# Sheet1.net
KiCad netlist of a schematic drawn in Altium Designer
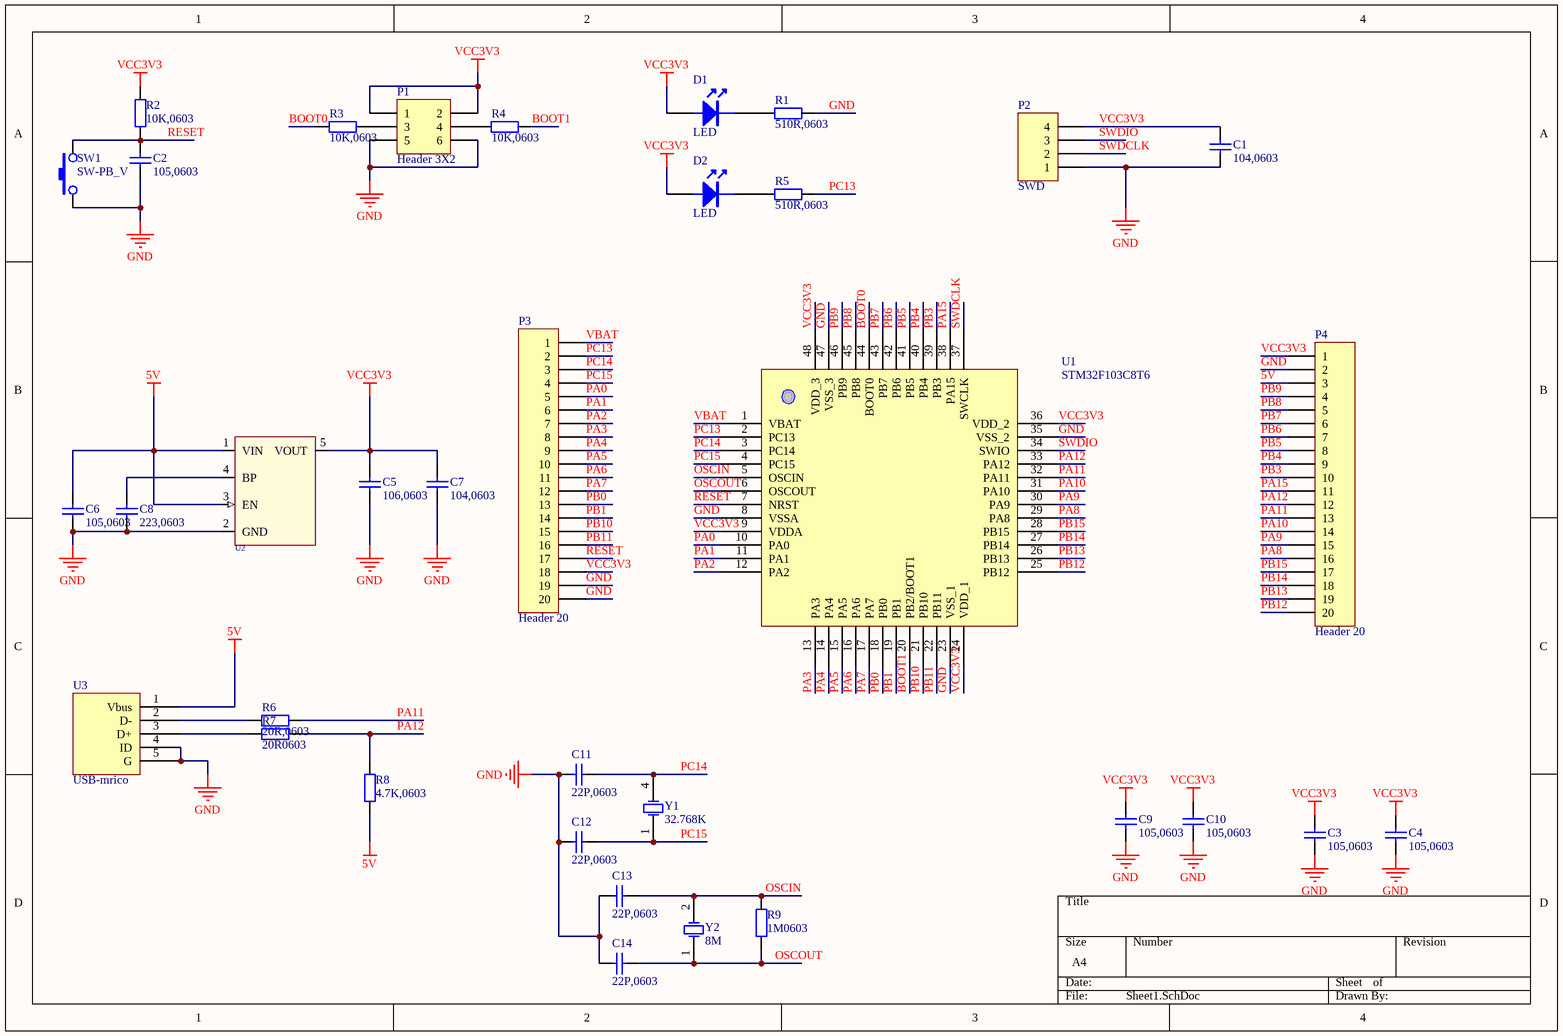
[diagram p0: Sheet1.SchDoc]

(export (version "E")
  (design (tool "Eeschema 10.0.6"))
  (components
    (comp (ref "C1")
      (value "104,0603")
      (footprint "C 0603")
      (description "Capacitor")
      (fields (field (name "PUBLISHER") "Altium Limited"))
      (libsource (lib "STM32F103C8T6") (part "Cap"))
    )
    (comp (ref "C2")
      (value "105,0603")
      (footprint "C 0603")
      (description "Capacitor")
      (fields (field (name "PUBLISHER") "Altium Limited"))
      (libsource (lib "STM32F103C8T6") (part "Cap"))
    )
    (comp (ref "C3")
      (value "105,0603")
      (footprint "C 0603")
      (description "Capacitor")
      (fields (field (name "PUBLISHER") "Altium Limited"))
      (libsource (lib "STM32F103C8T6") (part "Cap"))
    )
    (comp (ref "C4")
      (value "105,0603")
      (footprint "C 0603")
      (description "Capacitor")
      (fields (field (name "PUBLISHER") "Altium Limited"))
      (libsource (lib "STM32F103C8T6") (part "Cap"))
    )
    (comp (ref "C5")
      (value "106,0603")
      (footprint "C 0603")
      (description "Capacitor")
      (fields (field (name "PUBLISHER") "Altium Limited"))
      (libsource (lib "STM32F103C8T6") (part "Cap"))
    )
    (comp (ref "C6")
      (value "105,0603")
      (footprint "C 0603")
      (description "Capacitor")
      (fields (field (name "PUBLISHER") "Altium Limited"))
      (libsource (lib "STM32F103C8T6") (part "Cap"))
    )
    (comp (ref "C7")
      (value "104,0603")
      (footprint "C 0603")
      (description "Capacitor")
      (fields (field (name "PUBLISHER") "Altium Limited"))
      (libsource (lib "STM32F103C8T6") (part "Cap"))
    )
    (comp (ref "C8")
      (value "223,0603")
      (footprint "C 0603")
      (description "Capacitor")
      (fields (field (name "PUBLISHER") "Altium Limited"))
      (libsource (lib "STM32F103C8T6") (part "Cap"))
    )
    (comp (ref "C9")
      (value "105,0603")
      (footprint "C 0603")
      (description "Capacitor")
      (fields (field (name "PUBLISHER") "Altium Limited"))
      (libsource (lib "STM32F103C8T6") (part "Cap"))
    )
    (comp (ref "C10")
      (value "105,0603")
      (footprint "C 0603")
      (description "Capacitor")
      (fields (field (name "PUBLISHER") "Altium Limited"))
      (libsource (lib "STM32F103C8T6") (part "Cap"))
    )
    (comp (ref "C11")
      (value "22P,0603")
      (footprint "C 0603")
      (description "Capacitor")
      (fields (field (name "PUBLISHER") "Altium Limited"))
      (libsource (lib "STM32F103C8T6") (part "Cap"))
    )
    (comp (ref "C12")
      (value "22P,0603")
      (footprint "C 0603")
      (description "Capacitor")
      (fields (field (name "PUBLISHER") "Altium Limited"))
      (libsource (lib "STM32F103C8T6") (part "Cap"))
    )
    (comp (ref "C13")
      (value "22P,0603")
      (footprint "C 0603")
      (description "Capacitor")
      (fields (field (name "PUBLISHER") "Altium Limited"))
      (libsource (lib "STM32F103C8T6") (part "Cap"))
    )
    (comp (ref "C14")
      (value "22P,0603")
      (footprint "C 0603")
      (description "Capacitor")
      (fields (field (name "PUBLISHER") "Altium Limited"))
      (libsource (lib "STM32F103C8T6") (part "Cap"))
    )
    (comp (ref "D1") (value "LED") (footprint "LED 0805G") (libsource (lib "STM32F103C8T6") (part "LED")))
    (comp (ref "D2") (value "LED") (footprint "LED 0805G") (libsource (lib "STM32F103C8T6") (part "LED")))
    (comp (ref "P1")
      (value "Header 3X2")
      (footprint "HDR-3X2")
      (description "Header, 3-Pin, Dual row")
      (fields (field (name "PUBLISHER") "Altium Limited"))
      (libsource (lib "STM32F103C8T6") (part "Header 3X2"))
    )
    (comp (ref "P2")
      (value "SWD")
      (footprint "HDR-1X4_H")
      (description "Header, 4-Pin")
      (fields (field (name "PUBLISHER") "Altium Limited"))
      (libsource (lib "STM32F103C8T6") (part "Header 4"))
    )
    (comp (ref "P3")
      (value "Header 20")
      (footprint "HDR1X20")
      (description "Header, 20-Pin")
      (fields (field (name "PUBLISHER") "Altium Limited"))
      (libsource (lib "STM32F103C8T6") (part "Header 20"))
    )
    (comp (ref "P4")
      (value "Header 20")
      (footprint "HDR1X20")
      (description "Header, 20-Pin")
      (fields (field (name "PUBLISHER") "Altium Limited"))
      (libsource (lib "") (part "Header 20_1"))
    )
    (comp (ref "R1")
      (value "510R,0603")
      (footprint "R 0603")
      (description "Resistor")
      (fields (field (name "PUBLISHER") "Altium Limited"))
      (libsource (lib "") (part "Res2_1"))
    )
    (comp (ref "R2")
      (value "10K,0603")
      (footprint "R 0603")
      (description "Resistor")
      (fields (field (name "PUBLISHER") "Altium Limited"))
      (libsource (lib "STM32F103C8T6") (part "Res2"))
    )
    (comp (ref "R3")
      (value "10K,0603")
      (footprint "R 0603")
      (description "Resistor")
      (fields (field (name "PUBLISHER") "Altium Limited"))
      (libsource (lib "") (part "Res2_1"))
    )
    (comp (ref "R4")
      (value "10K,0603")
      (footprint "R 0603")
      (description "Resistor")
      (fields (field (name "PUBLISHER") "Altium Limited"))
      (libsource (lib "") (part "Res2_1"))
    )
    (comp (ref "R5")
      (value "510R,0603")
      (footprint "R 0603")
      (description "Resistor")
      (fields (field (name "PUBLISHER") "Altium Limited"))
      (libsource (lib "") (part "Res2_1"))
    )
    (comp (ref "R6")
      (value "20R,0603")
      (footprint "R 0603")
      (description "Resistor")
      (fields (field (name "PUBLISHER") "Altium Limited"))
      (libsource (lib "") (part "Res2_1"))
    )
    (comp (ref "R7")
      (value "20R0603")
      (footprint "R 0603")
      (description "Resistor")
      (fields (field (name "PUBLISHER") "Altium Limited"))
      (libsource (lib "") (part "Res2_1"))
    )
    (comp (ref "R8")
      (value "4.7K,0603")
      (footprint "R 0603")
      (description "Resistor")
      (fields (field (name "PUBLISHER") "Altium Limited"))
      (libsource (lib "STM32F103C8T6") (part "Res2"))
    )
    (comp (ref "R9")
      (value "1M0603")
      (footprint "R 0603")
      (description "Resistor")
      (fields (field (name "PUBLISHER") "Altium Limited"))
      (libsource (lib "STM32F103C8T6") (part "Res2"))
    )
    (comp (ref "SW1")
      (value "SW-PB_V")
      (footprint "TSW SMD-3*6*2.5")
      (description "SWITCH")
      (libsource (lib "STM32F103C8T6") (part "SW-PB_V"))
    )
    (comp (ref "U1")
      (value "STM32F103C8T6")
      (footprint "TQFP48 7x7_L")
      (libsource (lib "STM32F103C8T6") (part "STM32F103C8T6"))
    )
    (comp (ref "U2")
      (value "RT9193")
      (footprint "SOT23-5L")
      (fields (field (name "ICA_PARTNUM") "$$2191094$$RT9193-15CU5") (field (name "PART NUMBER") "TMP-13"))
      (libsource (lib "STM32F103C8T6") (part "RT9193X_5P"))
    )
    (comp (ref "U3")
      (value "USB-mrico")
      (footprint "USB-micro_B")
      (libsource (lib "PCB_Project_4") (part "usb-STM"))
    )
    (comp (ref "Y1")
      (value "32.768K")
      (footprint "MC-306")
      (description "Crystal Oscillator")
      (fields (field (name "PUBLISHER") "Altium Limited"))
      (libsource (lib "STM32F103C8T6") (part "XTAL"))
    )
    (comp (ref "Y2")
      (value "8M")
      (footprint "XTAL-49S DIP")
      (description "Crystal Oscillator")
      (fields (field (name "PUBLISHER") "Altium Limited"))
      (libsource (lib "") (part "XTAL_1"))
    )
  )
  (nets
    (net (code "1") (name "/BOOT0") (class "Default")
      (node (ref "R3") (pin "1") (pinfunction "1_1") (pintype "passive"))
      (node (ref "U1") (pin "44") (pinfunction "BOOT0_44") (pintype "passive"))
    )
    (net (code "2") (name "/BOOT1") (class "Default")
      (node (ref "R4") (pin "2") (pinfunction "2_2") (pintype "passive"))
      (node (ref "U1") (pin "20") (pinfunction "PB2/BOOT1_20") (pintype "passive"))
    )
    (net (code "3") (name "/OSCIN") (class "Default")
      (node (ref "C13") (pin "1") (pinfunction "1_1") (pintype "passive"))
      (node (ref "R9") (pin "2") (pinfunction "2_2") (pintype "passive"))
      (node (ref "U1") (pin "5") (pinfunction "OSCIN_5") (pintype "passive"))
      (node (ref "Y2") (pin "2") (pinfunction "OSC2_2") (pintype "passive"))
    )
    (net (code "4") (name "/OSCOUT") (class "Default")
      (node (ref "C14") (pin "1") (pinfunction "1_1") (pintype "passive"))
      (node (ref "R9") (pin "1") (pinfunction "1_1") (pintype "passive"))
      (node (ref "U1") (pin "6") (pinfunction "OSCOUT_6") (pintype "passive"))
      (node (ref "Y2") (pin "1") (pinfunction "OSC1_1") (pintype "passive"))
    )
    (net (code "5") (name "/PA0") (class "Default")
      (node (ref "P3") (pin "5") (pinfunction "5_5") (pintype "passive"))
      (node (ref "U1") (pin "10") (pinfunction "PA0_10") (pintype "passive"))
    )
    (net (code "6") (name "/PA1") (class "Default")
      (node (ref "P3") (pin "6") (pinfunction "6_6") (pintype "passive"))
      (node (ref "U1") (pin "11") (pinfunction "PA1_11") (pintype "passive"))
    )
    (net (code "7") (name "/PA2") (class "Default")
      (node (ref "P3") (pin "7") (pinfunction "7_7") (pintype "passive"))
      (node (ref "U1") (pin "12") (pinfunction "PA2_12") (pintype "passive"))
    )
    (net (code "8") (name "/PA3") (class "Default")
      (node (ref "P3") (pin "8") (pinfunction "8_8") (pintype "passive"))
      (node (ref "U1") (pin "13") (pinfunction "PA3_13") (pintype "passive"))
    )
    (net (code "9") (name "/PA4") (class "Default")
      (node (ref "P3") (pin "9") (pinfunction "9_9") (pintype "passive"))
      (node (ref "U1") (pin "14") (pinfunction "PA4_14") (pintype "passive"))
    )
    (net (code "10") (name "/PA5") (class "Default")
      (node (ref "P3") (pin "10") (pinfunction "10_10") (pintype "passive"))
      (node (ref "U1") (pin "15") (pinfunction "PA5_15") (pintype "passive"))
    )
    (net (code "11") (name "/PA6") (class "Default")
      (node (ref "P3") (pin "11") (pinfunction "11_11") (pintype "passive"))
      (node (ref "U1") (pin "16") (pinfunction "PA6_16") (pintype "passive"))
    )
    (net (code "12") (name "/PA7") (class "Default")
      (node (ref "P3") (pin "12") (pinfunction "12_12") (pintype "passive"))
      (node (ref "U1") (pin "17") (pinfunction "PA7_17") (pintype "passive"))
    )
    (net (code "13") (name "/PA8") (class "Default")
      (node (ref "P4") (pin "16") (pinfunction "16_16") (pintype "passive"))
      (node (ref "U1") (pin "29") (pinfunction "PA8_29") (pintype "passive"))
    )
    (net (code "14") (name "/PA9") (class "Default")
      (node (ref "P4") (pin "15") (pinfunction "15_15") (pintype "passive"))
      (node (ref "U1") (pin "30") (pinfunction "PA9_30") (pintype "passive"))
    )
    (net (code "15") (name "/PA10") (class "Default")
      (node (ref "P4") (pin "14") (pinfunction "14_14") (pintype "passive"))
      (node (ref "U1") (pin "31") (pinfunction "PA10_31") (pintype "passive"))
    )
    (net (code "16") (name "/PA11") (class "Default")
      (node (ref "P4") (pin "13") (pinfunction "13_13") (pintype "passive"))
      (node (ref "R6") (pin "2") (pinfunction "2_2") (pintype "passive"))
      (node (ref "U1") (pin "32") (pinfunction "PA11_32") (pintype "passive"))
    )
    (net (code "17") (name "/PA12") (class "Default")
      (node (ref "P4") (pin "12") (pinfunction "12_12") (pintype "passive"))
      (node (ref "R7") (pin "2") (pinfunction "2_2") (pintype "passive"))
      (node (ref "R8") (pin "2") (pinfunction "2_2") (pintype "passive"))
      (node (ref "U1") (pin "33") (pinfunction "PA12_33") (pintype "passive"))
    )
    (net (code "18") (name "/PA15") (class "Default")
      (node (ref "P4") (pin "11") (pinfunction "11_11") (pintype "passive"))
      (node (ref "U1") (pin "38") (pinfunction "PA15_38") (pintype "passive"))
    )
    (net (code "19") (name "/PB0") (class "Default")
      (node (ref "P3") (pin "13") (pinfunction "13_13") (pintype "passive"))
      (node (ref "U1") (pin "18") (pinfunction "PB0_18") (pintype "passive"))
    )
    (net (code "20") (name "/PB1") (class "Default")
      (node (ref "P3") (pin "14") (pinfunction "14_14") (pintype "passive"))
      (node (ref "U1") (pin "19") (pinfunction "PB1_19") (pintype "passive"))
    )
    (net (code "21") (name "/PB3") (class "Default")
      (node (ref "P4") (pin "10") (pinfunction "10_10") (pintype "passive"))
      (node (ref "U1") (pin "39") (pinfunction "PB3_39") (pintype "passive"))
    )
    (net (code "22") (name "/PB4") (class "Default")
      (node (ref "P4") (pin "9") (pinfunction "9_9") (pintype "passive"))
      (node (ref "U1") (pin "40") (pinfunction "PB4_40") (pintype "passive"))
    )
    (net (code "23") (name "/PB5") (class "Default")
      (node (ref "P4") (pin "8") (pinfunction "8_8") (pintype "passive"))
      (node (ref "U1") (pin "41") (pinfunction "PB5_41") (pintype "passive"))
    )
    (net (code "24") (name "/PB6") (class "Default")
      (node (ref "P4") (pin "7") (pinfunction "7_7") (pintype "passive"))
      (node (ref "U1") (pin "42") (pinfunction "PB6_42") (pintype "passive"))
    )
    (net (code "25") (name "/PB7") (class "Default")
      (node (ref "P4") (pin "6") (pinfunction "6_6") (pintype "passive"))
      (node (ref "U1") (pin "43") (pinfunction "PB7_43") (pintype "passive"))
    )
    (net (code "26") (name "/PB8") (class "Default")
      (node (ref "P4") (pin "5") (pinfunction "5_5") (pintype "passive"))
      (node (ref "U1") (pin "45") (pinfunction "PB8_45") (pintype "passive"))
    )
    (net (code "27") (name "/PB9") (class "Default")
      (node (ref "P4") (pin "4") (pinfunction "4_4") (pintype "passive"))
      (node (ref "U1") (pin "46") (pinfunction "PB9_46") (pintype "passive"))
    )
    (net (code "28") (name "/PB10") (class "Default")
      (node (ref "P3") (pin "15") (pinfunction "15_15") (pintype "passive"))
      (node (ref "U1") (pin "21") (pinfunction "PB10_21") (pintype "passive"))
    )
    (net (code "29") (name "/PB11") (class "Default")
      (node (ref "P3") (pin "16") (pinfunction "16_16") (pintype "passive"))
      (node (ref "U1") (pin "22") (pinfunction "PB11_22") (pintype "passive"))
    )
    (net (code "30") (name "/PB12") (class "Default")
      (node (ref "P4") (pin "20") (pinfunction "20_20") (pintype "passive"))
      (node (ref "U1") (pin "25") (pinfunction "PB12_25") (pintype "passive"))
    )
    (net (code "31") (name "/PB13") (class "Default")
      (node (ref "P4") (pin "19") (pinfunction "19_19") (pintype "passive"))
      (node (ref "U1") (pin "26") (pinfunction "PB13_26") (pintype "passive"))
    )
    (net (code "32") (name "/PB14") (class "Default")
      (node (ref "P4") (pin "18") (pinfunction "18_18") (pintype "passive"))
      (node (ref "U1") (pin "27") (pinfunction "PB14_27") (pintype "passive"))
    )
    (net (code "33") (name "/PB15") (class "Default")
      (node (ref "P4") (pin "17") (pinfunction "17_17") (pintype "passive"))
      (node (ref "U1") (pin "28") (pinfunction "PB15_28") (pintype "passive"))
    )
    (net (code "34") (name "/PC13") (class "Default")
      (node (ref "P3") (pin "2") (pinfunction "2_2") (pintype "passive"))
      (node (ref "R5") (pin "2") (pinfunction "2_2") (pintype "passive"))
      (node (ref "U1") (pin "2") (pinfunction "PC13_2") (pintype "passive"))
    )
    (net (code "35") (name "/PC14") (class "Default")
      (node (ref "C11") (pin "1") (pinfunction "1_1") (pintype "passive"))
      (node (ref "P3") (pin "3") (pinfunction "3_3") (pintype "passive"))
      (node (ref "U1") (pin "3") (pinfunction "PC14_3") (pintype "passive"))
      (node (ref "Y1") (pin "4") (pinfunction "OSC2_4") (pintype "passive"))
    )
    (net (code "36") (name "/PC15") (class "Default")
      (node (ref "C12") (pin "1") (pinfunction "1_1") (pintype "passive"))
      (node (ref "P3") (pin "4") (pinfunction "4_4") (pintype "passive"))
      (node (ref "U1") (pin "4") (pinfunction "PC15_4") (pintype "passive"))
      (node (ref "Y1") (pin "1") (pinfunction "OSC1_1") (pintype "passive"))
    )
    (net (code "37") (name "/RESET") (class "Default")
      (node (ref "C2") (pin "2") (pinfunction "2_2") (pintype "passive"))
      (node (ref "P3") (pin "17") (pinfunction "17_17") (pintype "passive"))
      (node (ref "R2") (pin "1") (pinfunction "1_1") (pintype "passive"))
      (node (ref "SW1") (pin "2") (pinfunction "2_2") (pintype "passive"))
      (node (ref "U1") (pin "7") (pinfunction "NRST_7") (pintype "passive"))
    )
    (net (code "38") (name "/SWDCLK") (class "Default")
      (node (ref "P2") (pin "2") (pinfunction "2_2") (pintype "passive"))
      (node (ref "U1") (pin "37") (pinfunction "SWCLK_37") (pintype "passive"))
    )
    (net (code "39") (name "/SWDIO") (class "Default")
      (node (ref "P2") (pin "3") (pinfunction "3_3") (pintype "passive"))
      (node (ref "U1") (pin "34") (pinfunction "SWIO_34") (pintype "passive"))
    )
    (net (code "40") (name "/VBAT") (class "Default")
      (node (ref "P3") (pin "1") (pinfunction "1_1") (pintype "passive"))
      (node (ref "U1") (pin "1") (pinfunction "VBAT_1") (pintype "passive"))
    )
    (net (code "41") (name "5V") (class "Default")
      (node (ref "C6") (pin "2") (pinfunction "2_2") (pintype "passive"))
      (node (ref "P4") (pin "3") (pinfunction "3_3") (pintype "passive"))
      (node (ref "R8") (pin "1") (pinfunction "1_1") (pintype "passive"))
      (node (ref "U2") (pin "1") (pinfunction "VIN_1") (pintype "power_in"))
      (node (ref "U2") (pin "3") (pinfunction "EN_3") (pintype "input"))
      (node (ref "U3") (pin "1") (pinfunction "Vbus_1") (pintype "passive"))
    )
    (net (code "42") (name "GND") (class "Default")
      (node (ref "C1") (pin "1") (pinfunction "1_1") (pintype "passive"))
      (node (ref "C10") (pin "1") (pinfunction "1_1") (pintype "passive"))
      (node (ref "C11") (pin "2") (pinfunction "2_2") (pintype "passive"))
      (node (ref "C12") (pin "2") (pinfunction "2_2") (pintype "passive"))
      (node (ref "C13") (pin "2") (pinfunction "2_2") (pintype "passive"))
      (node (ref "C14") (pin "2") (pinfunction "2_2") (pintype "passive"))
      (node (ref "C2") (pin "1") (pinfunction "1_1") (pintype "passive"))
      (node (ref "C3") (pin "1") (pinfunction "1_1") (pintype "passive"))
      (node (ref "C4") (pin "1") (pinfunction "1_1") (pintype "passive"))
      (node (ref "C5") (pin "2") (pinfunction "2_2") (pintype "passive"))
      (node (ref "C6") (pin "1") (pinfunction "1_1") (pintype "passive"))
      (node (ref "C7") (pin "1") (pinfunction "1_1") (pintype "passive"))
      (node (ref "C8") (pin "1") (pinfunction "1_1") (pintype "passive"))
      (node (ref "C9") (pin "1") (pinfunction "1_1") (pintype "passive"))
      (node (ref "P1") (pin "5") (pinfunction "5_5") (pintype "passive"))
      (node (ref "P1") (pin "6") (pinfunction "6_6") (pintype "passive"))
      (node (ref "P2") (pin "1") (pinfunction "1_1") (pintype "passive"))
      (node (ref "P3") (pin "19") (pinfunction "19_19") (pintype "passive"))
      (node (ref "P3") (pin "20") (pinfunction "20_20") (pintype "passive"))
      (node (ref "P4") (pin "2") (pinfunction "2_2") (pintype "passive"))
      (node (ref "R1") (pin "2") (pinfunction "2_2") (pintype "passive"))
      (node (ref "SW1") (pin "1") (pinfunction "1_1") (pintype "passive"))
      (node (ref "U1") (pin "23") (pinfunction "VSS_1_23") (pintype "passive"))
      (node (ref "U1") (pin "35") (pinfunction "VSS_2_35") (pintype "passive"))
      (node (ref "U1") (pin "47") (pinfunction "VSS_3_47") (pintype "passive"))
      (node (ref "U1") (pin "8") (pinfunction "VSSA_8") (pintype "passive"))
      (node (ref "U2") (pin "2") (pinfunction "GND_2") (pintype "power_in"))
      (node (ref "U3") (pin "4") (pinfunction "ID_4") (pintype "passive"))
      (node (ref "U3") (pin "5") (pinfunction "G_5") (pintype "passive"))
    )
    (net (code "43") (name "Net-(D1-Pad2)") (class "Default")
      (node (ref "D1") (pin "2") (pinfunction "2_2") (pintype "passive"))
      (node (ref "R1") (pin "1") (pinfunction "1_1") (pintype "passive"))
    )
    (net (code "44") (name "Net-(D2-Pad2)") (class "Default")
      (node (ref "D2") (pin "2") (pinfunction "2_2") (pintype "passive"))
      (node (ref "R5") (pin "1") (pinfunction "1_1") (pintype "passive"))
    )
    (net (code "45") (name "Net-(P1-Pad3)") (class "Default")
      (node (ref "P1") (pin "3") (pinfunction "3_3") (pintype "passive"))
      (node (ref "R3") (pin "2") (pinfunction "2_2") (pintype "passive"))
    )
    (net (code "46") (name "Net-(P1-Pad4)") (class "Default")
      (node (ref "P1") (pin "4") (pinfunction "4_4") (pintype "passive"))
      (node (ref "R4") (pin "1") (pinfunction "1_1") (pintype "passive"))
    )
    (net (code "47") (name "Net-(U2-BP)") (class "Default")
      (node (ref "C8") (pin "2") (pinfunction "2_2") (pintype "passive"))
      (node (ref "U2") (pin "4") (pinfunction "BP_4") (pintype "passive"))
    )
    (net (code "48") (name "Net-(U3-D+)") (class "Default")
      (node (ref "R7") (pin "1") (pinfunction "1_1") (pintype "passive"))
      (node (ref "U3") (pin "3") (pinfunction "D+_3") (pintype "passive"))
    )
    (net (code "49") (name "Net-(U3-D-)") (class "Default")
      (node (ref "R6") (pin "1") (pinfunction "1_1") (pintype "passive"))
      (node (ref "U3") (pin "2") (pinfunction "D-_2") (pintype "passive"))
    )
    (net (code "50") (name "VCC3V3") (class "Default")
      (node (ref "C1") (pin "2") (pinfunction "2_2") (pintype "passive"))
      (node (ref "C10") (pin "2") (pinfunction "2_2") (pintype "passive"))
      (node (ref "C3") (pin "2") (pinfunction "2_2") (pintype "passive"))
      (node (ref "C4") (pin "2") (pinfunction "2_2") (pintype "passive"))
      (node (ref "C5") (pin "1") (pinfunction "1_1") (pintype "passive"))
      (node (ref "C7") (pin "2") (pinfunction "2_2") (pintype "passive"))
      (node (ref "C9") (pin "2") (pinfunction "2_2") (pintype "passive"))
      (node (ref "D1") (pin "1") (pinfunction "1_1") (pintype "passive"))
      (node (ref "D2") (pin "1") (pinfunction "1_1") (pintype "passive"))
      (node (ref "P1") (pin "1") (pinfunction "1_1") (pintype "passive"))
      (node (ref "P1") (pin "2") (pinfunction "2_2") (pintype "passive"))
      (node (ref "P2") (pin "4") (pinfunction "4_4") (pintype "passive"))
      (node (ref "P3") (pin "18") (pinfunction "18_18") (pintype "passive"))
      (node (ref "P4") (pin "1") (pinfunction "1_1") (pintype "passive"))
      (node (ref "R2") (pin "2") (pinfunction "2_2") (pintype "passive"))
      (node (ref "U1") (pin "24") (pinfunction "VDD_1_24") (pintype "passive"))
      (node (ref "U1") (pin "36") (pinfunction "VDD_2_36") (pintype "passive"))
      (node (ref "U1") (pin "48") (pinfunction "VDD_3_48") (pintype "passive"))
      (node (ref "U1") (pin "9") (pinfunction "VDDA_9") (pintype "passive"))
      (node (ref "U2") (pin "5") (pinfunction "VOUT_5") (pintype "power_in"))
    )
  )
)
